# stm32f407.net
KiCad netlist of a schematic drawn in EAGLE
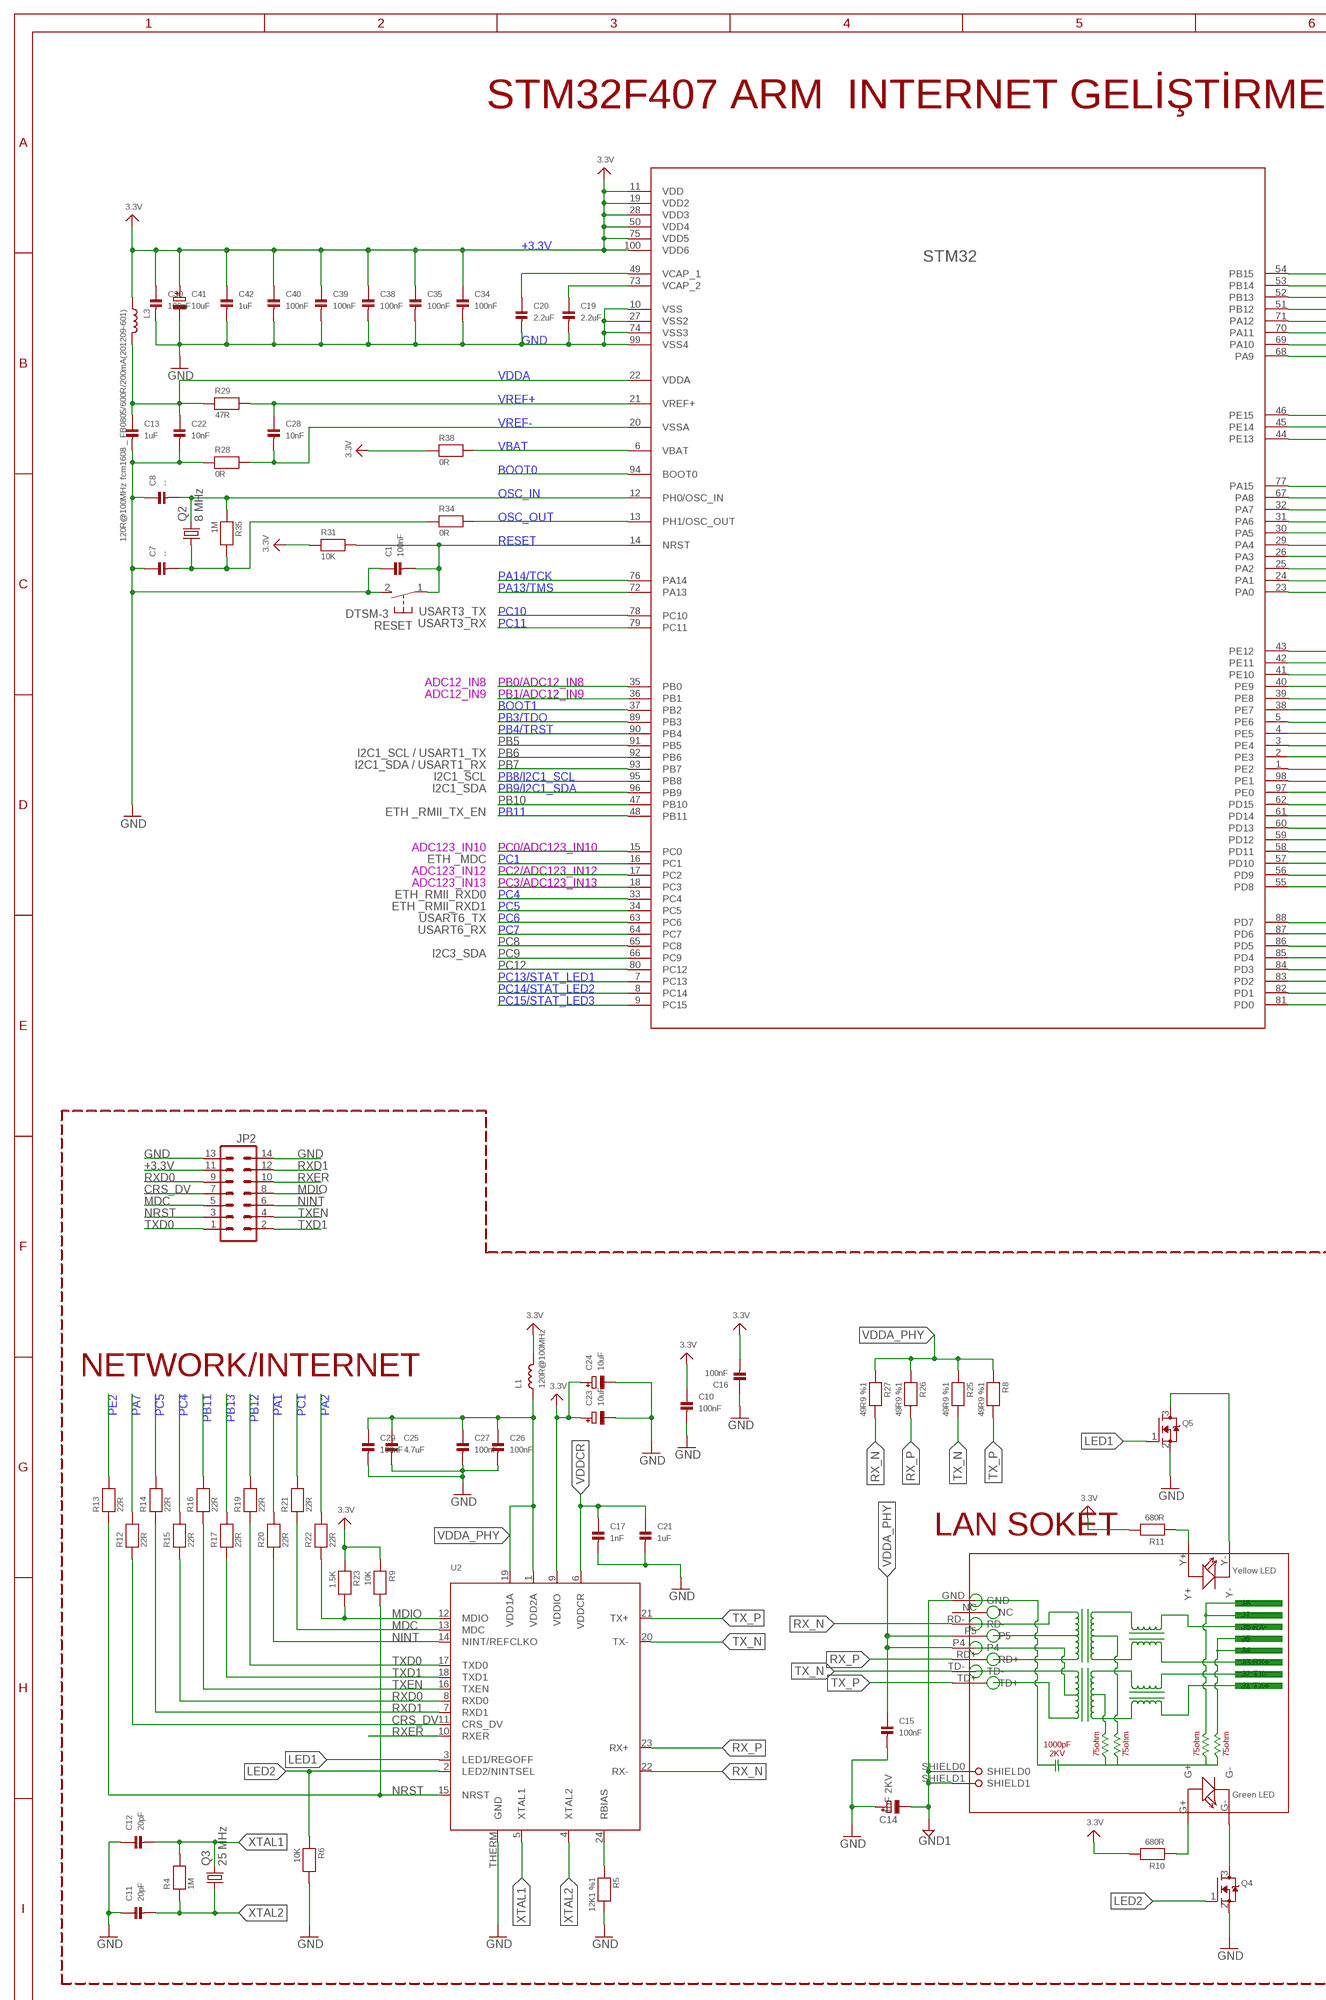
[diagram p0: schematic, sheet 1, part 1 of 2]
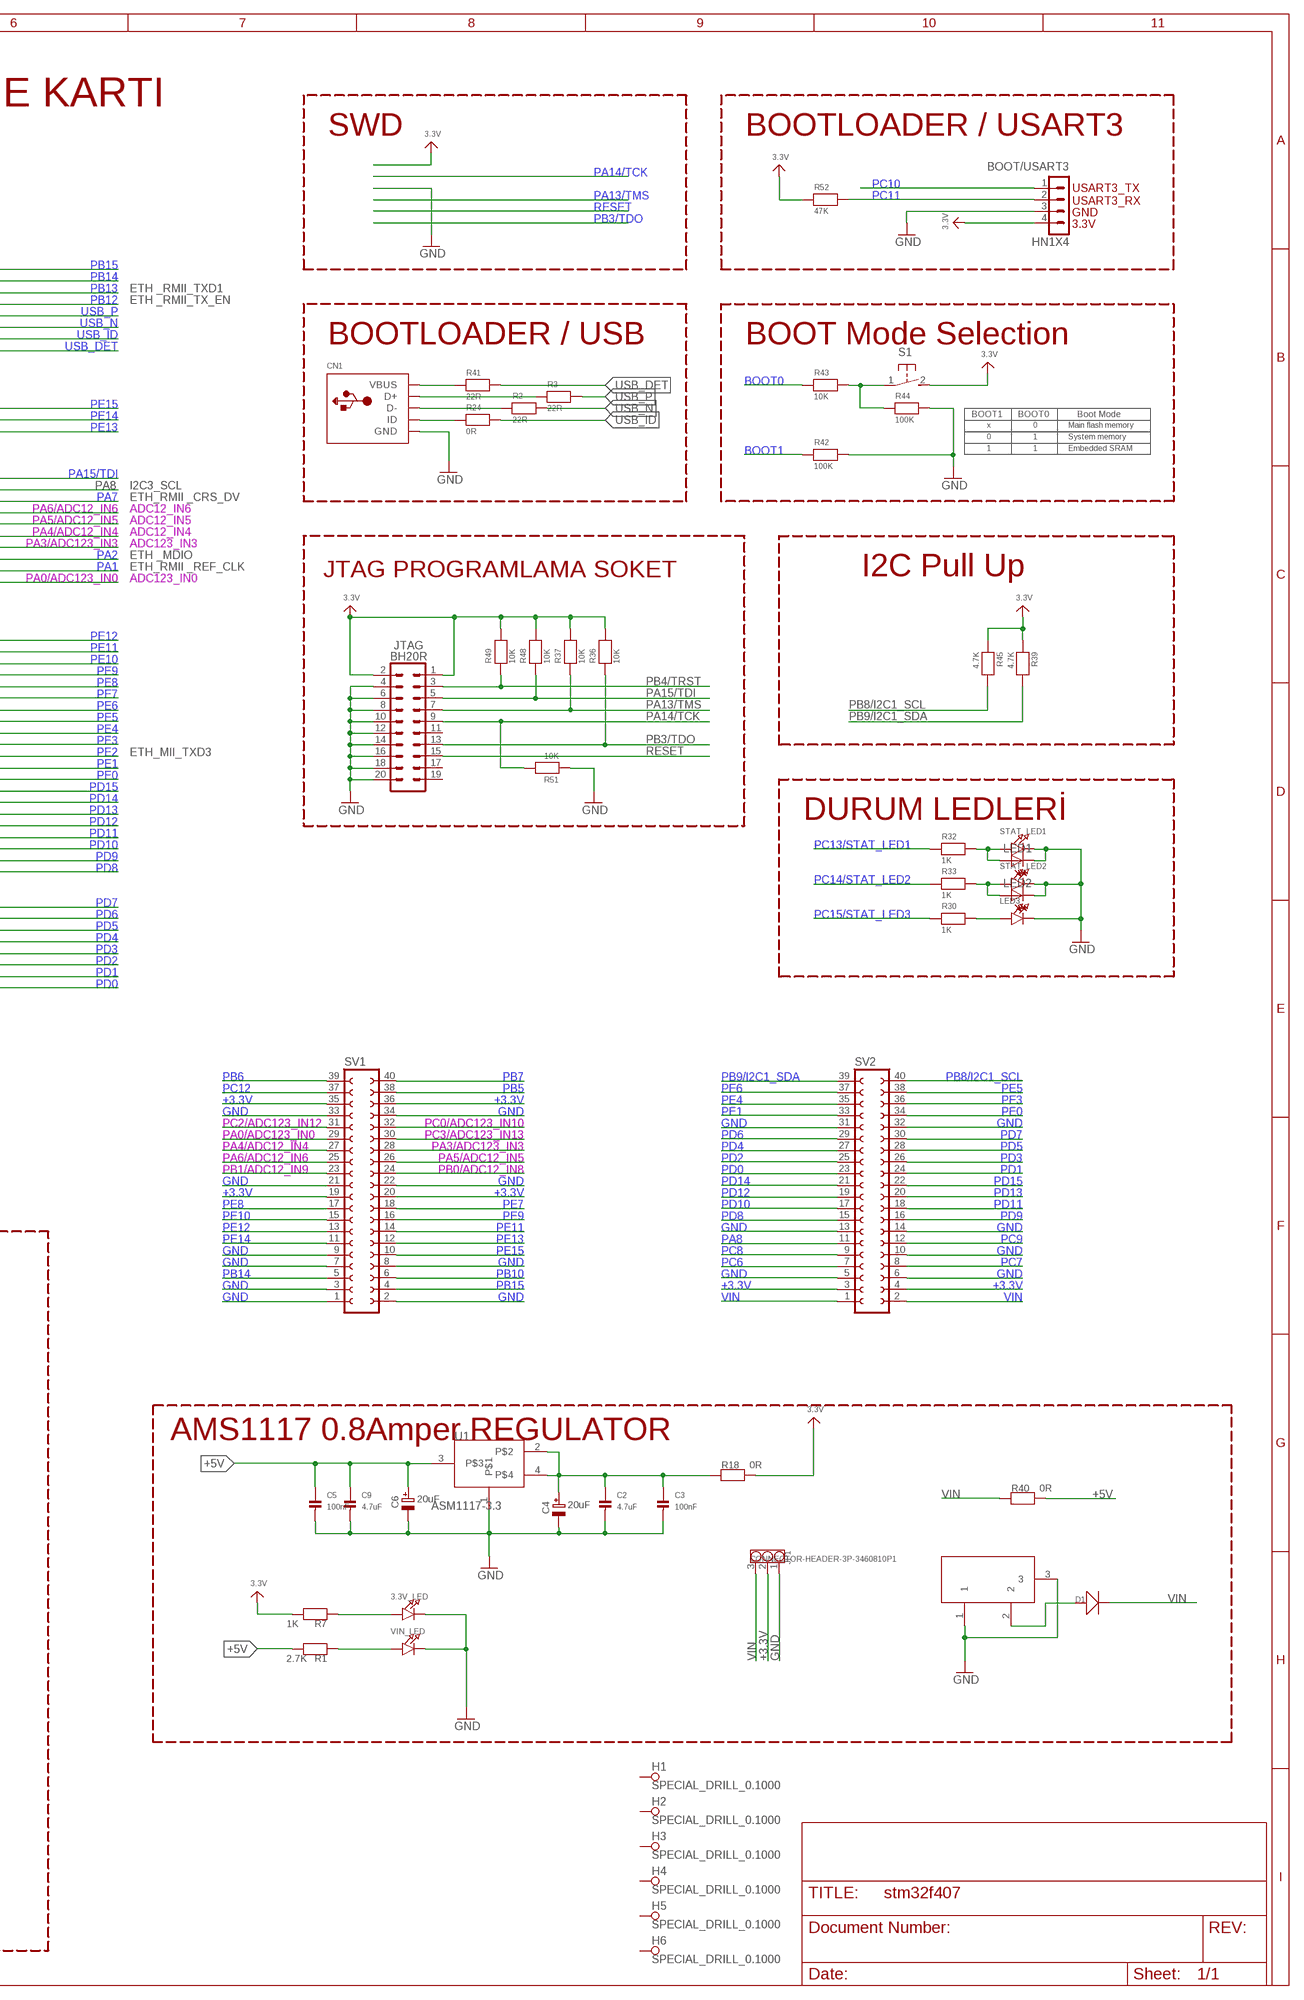
[diagram p1: schematic, sheet 1, part 2 of 2]

(export (version "E")
  (design (tool "Eeschema 10.0.6"))
  (components
    (comp (ref "3.3V_LED")
      (value "LED0805")
      (footprint "eagle-import:CHIPLED_0805")
      (libsource (lib "eagle-import") (part "LED0805"))
    )
    (comp (ref "BOOT/USART3")
      (value "HN1X4")
      (footprint "eagle-import:HN1X4")
      (libsource (lib "eagle-import") (part "CON4HN1X4"))
    )
    (comp (ref "C1")
      (value "100nF")
      (footprint "eagle-import:_0603")
      (libsource (lib "eagle-import") (part "CAP_CERAMIC_0603"))
    )
    (comp (ref "C2")
      (value "4.7uF")
      (footprint "eagle-import:0805")
      (libsource (lib "eagle-import") (part "CAP_CERAMIC0805"))
    )
    (comp (ref "C3")
      (value "100nF")
      (footprint "eagle-import:0805")
      (libsource (lib "eagle-import") (part "CAP_CERAMIC0805"))
    )
    (comp (ref "C4")
      (value "20uF")
      (footprint "eagle-import:EIA3528-21_B-R")
      (libsource (lib "eagle-import") (part "CAP_TANTALUMB/3528_REFLOW"))
    )
    (comp (ref "C5")
      (value "100nF")
      (footprint "eagle-import:0805")
      (libsource (lib "eagle-import") (part "CAP_CERAMIC0805"))
    )
    (comp (ref "C6")
      (value "20uF")
      (footprint "eagle-import:EIA3528-21_B-R")
      (libsource (lib "eagle-import") (part "CAP_TANTALUMB/3528_REFLOW"))
    )
    (comp (ref "C7")
      (value "--")
      (footprint "eagle-import:_0603")
      (libsource (lib "eagle-import") (part "CAP_CERAMIC_0603"))
    )
    (comp (ref "C8")
      (value "--")
      (footprint "eagle-import:_0603")
      (libsource (lib "eagle-import") (part "CAP_CERAMIC_0603"))
    )
    (comp (ref "C9")
      (value "4.7uF")
      (footprint "eagle-import:0805")
      (libsource (lib "eagle-import") (part "CAP_CERAMIC0805"))
    )
    (comp (ref "C10")
      (value "100nF")
      (footprint "eagle-import:_0603")
      (libsource (lib "eagle-import") (part "CAP_CERAMIC_0603"))
    )
    (comp (ref "C11")
      (value "20pF")
      (footprint "eagle-import:_0603")
      (libsource (lib "eagle-import") (part "CAP_CERAMIC_0603"))
    )
    (comp (ref "C12")
      (value "20pF")
      (footprint "eagle-import:_0603")
      (libsource (lib "eagle-import") (part "CAP_CERAMIC_0603"))
    )
    (comp (ref "C13")
      (value "1uF")
      (footprint "eagle-import:_0805")
      (libsource (lib "eagle-import") (part "CAP_CERAMIC_0805"))
    )
    (comp (ref "C14")
      (value "1nF 2KV")
      (footprint "eagle-import:EIA3528-21_B-R")
      (libsource (lib "eagle-import") (part "CAP_TANTALUMB/3528_REFLOW"))
    )
    (comp (ref "C15")
      (value "100nF")
      (footprint "eagle-import:_0805")
      (libsource (lib "eagle-import") (part "CAP_CERAMIC_0805"))
    )
    (comp (ref "C16")
      (value "100nF")
      (footprint "eagle-import:_0603")
      (libsource (lib "eagle-import") (part "CAP_CERAMIC_0603"))
    )
    (comp (ref "C17")
      (value "1nF")
      (footprint "eagle-import:_0603")
      (libsource (lib "eagle-import") (part "CAP_CERAMIC_0603"))
    )
    (comp (ref "C19")
      (value "2.2uF")
      (footprint "eagle-import:1206")
      (libsource (lib "eagle-import") (part "CAP_CERAMIC1206"))
    )
    (comp (ref "C20")
      (value "2.2uF")
      (footprint "eagle-import:1206")
      (libsource (lib "eagle-import") (part "CAP_CERAMIC1206"))
    )
    (comp (ref "C21")
      (value "1uF")
      (footprint "eagle-import:_0805")
      (libsource (lib "eagle-import") (part "CAP_CERAMIC_0805"))
    )
    (comp (ref "C22")
      (value "10nF")
      (footprint "eagle-import:_0603")
      (libsource (lib "eagle-import") (part "CAP_CERAMIC_0603"))
    )
    (comp (ref "C23")
      (value "10uF")
      (footprint "eagle-import:EIA3528-21_B-R")
      (libsource (lib "eagle-import") (part "CAP_TANTALUMB/3528_REFLOW"))
    )
    (comp (ref "C24")
      (value "10uF")
      (footprint "eagle-import:EIA3528-21_B-R")
      (libsource (lib "eagle-import") (part "CAP_TANTALUMB/3528_REFLOW"))
    )
    (comp (ref "C25")
      (value "4.7uF")
      (footprint "eagle-import:_0805")
      (libsource (lib "eagle-import") (part "CAP_CERAMIC_0805"))
    )
    (comp (ref "C26")
      (value "100nF")
      (footprint "eagle-import:_0603")
      (libsource (lib "eagle-import") (part "CAP_CERAMIC_0603"))
    )
    (comp (ref "C27")
      (value "100nF")
      (footprint "eagle-import:_0603")
      (libsource (lib "eagle-import") (part "CAP_CERAMIC_0603"))
    )
    (comp (ref "C28")
      (value "10nF")
      (footprint "eagle-import:_0603")
      (libsource (lib "eagle-import") (part "CAP_CERAMIC_0603"))
    )
    (comp (ref "C29")
      (value "100nF")
      (footprint "eagle-import:_0603")
      (libsource (lib "eagle-import") (part "CAP_CERAMIC_0603"))
    )
    (comp (ref "C30")
      (value "100nF")
      (footprint "eagle-import:_0603")
      (libsource (lib "eagle-import") (part "CAP_CERAMIC_0603"))
    )
    (comp (ref "C34")
      (value "100nF")
      (footprint "eagle-import:_0603")
      (libsource (lib "eagle-import") (part "CAP_CERAMIC_0603"))
    )
    (comp (ref "C35")
      (value "100nF")
      (footprint "eagle-import:_0603")
      (libsource (lib "eagle-import") (part "CAP_CERAMIC_0603"))
    )
    (comp (ref "C38")
      (value "100nF")
      (footprint "eagle-import:_0603")
      (libsource (lib "eagle-import") (part "CAP_CERAMIC_0603"))
    )
    (comp (ref "C39")
      (value "100nF")
      (footprint "eagle-import:_0603")
      (libsource (lib "eagle-import") (part "CAP_CERAMIC_0603"))
    )
    (comp (ref "C40")
      (value "100nF")
      (footprint "eagle-import:_0603")
      (libsource (lib "eagle-import") (part "CAP_CERAMIC_0603"))
    )
    (comp (ref "C41")
      (value "10uF")
      (footprint "eagle-import:EIA3528-21_B-R")
      (libsource (lib "eagle-import") (part "CAP_TANTALUMB/3528_REFLOW"))
    )
    (comp (ref "C42")
      (value "1uF")
      (footprint "eagle-import:_0805")
      (libsource (lib "eagle-import") (part "CAP_CERAMIC_0805"))
    )
    (comp (ref "CN1")
      (value "USBMINIBLARGE")
      (footprint "eagle-import:USB-MINIB_LARGER")
      (libsource (lib "eagle-import") (part "USBMINIBLARGE"))
    )
    (comp (ref "D1")
      (value "D-D1206")
      (footprint "eagle-import:LL-34")
      (libsource (lib "eagle-import") (part "D-D1206"))
    )
    (comp (ref "H1")
      (value "SPECIAL_DRILL_0.1000")
      (footprint "eagle-import:PAD_0.1000")
      (libsource (lib "eagle-import") (part "SPECIAL_DRILL_0.1000"))
    )
    (comp (ref "H2")
      (value "SPECIAL_DRILL_0.1000")
      (footprint "eagle-import:PAD_0.1000")
      (libsource (lib "eagle-import") (part "SPECIAL_DRILL_0.1000"))
    )
    (comp (ref "H3")
      (value "SPECIAL_DRILL_0.1000")
      (footprint "eagle-import:PAD_0.1000")
      (libsource (lib "eagle-import") (part "SPECIAL_DRILL_0.1000"))
    )
    (comp (ref "H4")
      (value "SPECIAL_DRILL_0.1000")
      (footprint "eagle-import:PAD_0.1000")
      (libsource (lib "eagle-import") (part "SPECIAL_DRILL_0.1000"))
    )
    (comp (ref "H5")
      (value "SPECIAL_DRILL_0.1000")
      (footprint "eagle-import:PAD_0.1000")
      (libsource (lib "eagle-import") (part "SPECIAL_DRILL_0.1000"))
    )
    (comp (ref "H6")
      (value "SPECIAL_DRILL_0.1000")
      (footprint "eagle-import:PAD_0.1000")
      (libsource (lib "eagle-import") (part "SPECIAL_DRILL_0.1000"))
    )
    (comp (ref "JP1")
      (value "CONNECTOR-HEADER-3P-3460810P1")
      (footprint "eagle-import:1X3P-2.54-2.54-11.6-3.0-BLACK-MALE")
      (libsource (lib "eagle-import") (part "CONNECTOR-HEADER-3P-3460810P1"))
    )
    (comp (ref "JP2")
      (value "MA07-2")
      (footprint "eagle-import:MA07-2")
      (libsource (lib "eagle-import") (part "MA07-2"))
    )
    (comp (ref "JTAG")
      (value "BH20R")
      (footprint "eagle-import:BH20R")
      (libsource (lib "eagle-import") (part "ML20R"))
    )
    (comp (ref "L1")
      (value "120R@100MHz")
      (footprint "eagle-import:_0805")
      (libsource (lib "eagle-import") (part "INDUCTOR_0805"))
    )
    (comp (ref "L3")
      (value "120R@100MHz fcm1608 _ FB0805/600R/200mA(201209-601)")
      (footprint "eagle-import:_0805")
      (libsource (lib "eagle-import") (part "INDUCTOR_0805"))
    )
    (comp (ref "LED1")
      (value "LED5MM")
      (footprint "eagle-import:LED5MM")
      (libsource (lib "eagle-import") (part "LED5MM"))
    )
    (comp (ref "LED2")
      (value "LED5MM")
      (footprint "eagle-import:LED5MM")
      (libsource (lib "eagle-import") (part "LED5MM"))
    )
    (comp (ref "LED3")
      (value "LED0805")
      (footprint "eagle-import:CHIPLED_0805")
      (libsource (lib "eagle-import") (part "LED0805"))
    )
    (comp (ref "Q2")
      (value "8 MHz")
      (footprint "eagle-import:HC49UP")
      (libsource (lib "eagle-import") (part "CRYSTALHC49UP"))
    )
    (comp (ref "Q3")
      (value "25 MHz")
      (footprint "eagle-import:HC49UP")
      (libsource (lib "eagle-import") (part "CRYSTALHC49UP"))
    )
    (comp (ref "Q4")
      (value "MOSFET-NWIDE")
      (footprint "eagle-import:SOT23-WIDE")
      (libsource (lib "eagle-import") (part "MOSFET-NWIDE"))
    )
    (comp (ref "Q5")
      (value "MOSFET-NWIDE")
      (footprint "eagle-import:SOT23-WIDE")
      (libsource (lib "eagle-import") (part "MOSFET-NWIDE"))
    )
    (comp (ref "R1")
      (value "2.7K")
      (footprint "eagle-import:_0603")
      (libsource (lib "eagle-import") (part "RESISTOR_0603"))
    )
    (comp (ref "R2")
      (value "22R")
      (footprint "eagle-import:_0603")
      (libsource (lib "eagle-import") (part "RESISTOR_0603"))
    )
    (comp (ref "R3")
      (value "22R")
      (footprint "eagle-import:_0603")
      (libsource (lib "eagle-import") (part "RESISTOR_0603"))
    )
    (comp (ref "R4")
      (value "1M")
      (footprint "eagle-import:_0603")
      (libsource (lib "eagle-import") (part "RESISTOR_0603"))
    )
    (comp (ref "R5")
      (value "12K1 %1")
      (footprint "eagle-import:_0603")
      (libsource (lib "eagle-import") (part "RESISTOR_0603"))
    )
    (comp (ref "R6")
      (value "10K")
      (footprint "eagle-import:_0603")
      (libsource (lib "eagle-import") (part "RESISTOR_0603"))
    )
    (comp (ref "R7")
      (value "1K")
      (footprint "eagle-import:_0603")
      (libsource (lib "eagle-import") (part "RESISTOR_0603"))
    )
    (comp (ref "R8")
      (value "49R9 %1")
      (footprint "eagle-import:_0603")
      (libsource (lib "eagle-import") (part "RESISTOR_0603"))
    )
    (comp (ref "R9")
      (value "10K")
      (footprint "eagle-import:_0603")
      (libsource (lib "eagle-import") (part "RESISTOR_0603"))
    )
    (comp (ref "R10")
      (value "680R")
      (footprint "eagle-import:_0805")
      (libsource (lib "eagle-import") (part "RESISTOR_0805"))
    )
    (comp (ref "R11")
      (value "680R")
      (footprint "eagle-import:_0805")
      (libsource (lib "eagle-import") (part "RESISTOR_0805"))
    )
    (comp (ref "R12")
      (value "22R")
      (footprint "eagle-import:_0603")
      (libsource (lib "eagle-import") (part "RESISTOR_0603"))
    )
    (comp (ref "R13")
      (value "22R")
      (footprint "eagle-import:_0603")
      (libsource (lib "eagle-import") (part "RESISTOR_0603"))
    )
    (comp (ref "R14")
      (value "22R")
      (footprint "eagle-import:_0603")
      (libsource (lib "eagle-import") (part "RESISTOR_0603"))
    )
    (comp (ref "R15")
      (value "22R")
      (footprint "eagle-import:_0603")
      (libsource (lib "eagle-import") (part "RESISTOR_0603"))
    )
    (comp (ref "R16")
      (value "22R")
      (footprint "eagle-import:_0603")
      (libsource (lib "eagle-import") (part "RESISTOR_0603"))
    )
    (comp (ref "R17")
      (value "22R")
      (footprint "eagle-import:_0603")
      (libsource (lib "eagle-import") (part "RESISTOR_0603"))
    )
    (comp (ref "R18")
      (value "0R")
      (footprint "eagle-import:0805")
      (libsource (lib "eagle-import") (part "RESISTOR0805"))
    )
    (comp (ref "R19")
      (value "22R")
      (footprint "eagle-import:_0603")
      (libsource (lib "eagle-import") (part "RESISTOR_0603"))
    )
    (comp (ref "R20")
      (value "22R")
      (footprint "eagle-import:_0603")
      (libsource (lib "eagle-import") (part "RESISTOR_0603"))
    )
    (comp (ref "R21")
      (value "22R")
      (footprint "eagle-import:_0603")
      (libsource (lib "eagle-import") (part "RESISTOR_0603"))
    )
    (comp (ref "R22")
      (value "22R")
      (footprint "eagle-import:_0603")
      (libsource (lib "eagle-import") (part "RESISTOR_0603"))
    )
    (comp (ref "R23")
      (value "1.5K")
      (footprint "eagle-import:_0603")
      (libsource (lib "eagle-import") (part "RESISTOR_0603"))
    )
    (comp (ref "R24")
      (value "0R")
      (footprint "eagle-import:_0603")
      (libsource (lib "eagle-import") (part "RESISTOR_0603"))
    )
    (comp (ref "R25")
      (value "49R9 %1")
      (footprint "eagle-import:_0603")
      (libsource (lib "eagle-import") (part "RESISTOR_0603"))
    )
    (comp (ref "R26")
      (value "49R9 %1")
      (footprint "eagle-import:_0603")
      (libsource (lib "eagle-import") (part "RESISTOR_0603"))
    )
    (comp (ref "R27")
      (value "49R9 %1")
      (footprint "eagle-import:_0603")
      (libsource (lib "eagle-import") (part "RESISTOR_0603"))
    )
    (comp (ref "R28")
      (value "0R")
      (footprint "eagle-import:_0603")
      (libsource (lib "eagle-import") (part "RESISTOR_0603"))
    )
    (comp (ref "R29")
      (value "47R")
      (footprint "eagle-import:_0603")
      (libsource (lib "eagle-import") (part "RESISTOR_0603"))
    )
    (comp (ref "R30")
      (value "1K")
      (footprint "eagle-import:_0603")
      (libsource (lib "eagle-import") (part "RESISTOR_0603"))
    )
    (comp (ref "R31")
      (value "10K")
      (footprint "eagle-import:_0603")
      (libsource (lib "eagle-import") (part "RESISTOR_0603"))
    )
    (comp (ref "R32")
      (value "1K")
      (footprint "eagle-import:_0603")
      (libsource (lib "eagle-import") (part "RESISTOR_0603"))
    )
    (comp (ref "R33")
      (value "1K")
      (footprint "eagle-import:_0603")
      (libsource (lib "eagle-import") (part "RESISTOR_0603"))
    )
    (comp (ref "R34")
      (value "0R")
      (footprint "eagle-import:_0603")
      (libsource (lib "eagle-import") (part "RESISTOR_0603"))
    )
    (comp (ref "R35")
      (value "1M")
      (footprint "eagle-import:_0603")
      (libsource (lib "eagle-import") (part "RESISTOR_0603"))
    )
    (comp (ref "R36")
      (value "10K")
      (footprint "eagle-import:_0603")
      (libsource (lib "eagle-import") (part "RESISTOR_0603"))
    )
    (comp (ref "R37")
      (value "10K")
      (footprint "eagle-import:_0603")
      (libsource (lib "eagle-import") (part "RESISTOR_0603"))
    )
    (comp (ref "R38")
      (value "0R")
      (footprint "eagle-import:_0603")
      (libsource (lib "eagle-import") (part "RESISTOR_0603"))
    )
    (comp (ref "R39")
      (value "4.7K")
      (footprint "eagle-import:1206")
      (libsource (lib "eagle-import") (part "RESISTOR1206"))
    )
    (comp (ref "R40")
      (value "0R")
      (footprint "eagle-import:0805")
      (libsource (lib "eagle-import") (part "RESISTOR0805"))
    )
    (comp (ref "R41")
      (value "22R")
      (footprint "eagle-import:_0603")
      (libsource (lib "eagle-import") (part "RESISTOR_0603"))
    )
    (comp (ref "R42")
      (value "100K")
      (footprint "eagle-import:_0603")
      (libsource (lib "eagle-import") (part "RESISTOR_0603"))
    )
    (comp (ref "R43")
      (value "10K")
      (footprint "eagle-import:_0603")
      (libsource (lib "eagle-import") (part "RESISTOR_0603"))
    )
    (comp (ref "R44")
      (value "100K")
      (footprint "eagle-import:_0603")
      (libsource (lib "eagle-import") (part "RESISTOR_0603"))
    )
    (comp (ref "R45")
      (value "4.7K")
      (footprint "eagle-import:1206")
      (libsource (lib "eagle-import") (part "RESISTOR1206"))
    )
    (comp (ref "R48")
      (value "10K")
      (footprint "eagle-import:_0603")
      (libsource (lib "eagle-import") (part "RESISTOR_0603"))
    )
    (comp (ref "R49")
      (value "10K")
      (footprint "eagle-import:_0603")
      (libsource (lib "eagle-import") (part "RESISTOR_0603"))
    )
    (comp (ref "R51")
      (value "10K")
      (footprint "eagle-import:_0603")
      (libsource (lib "eagle-import") (part "RESISTOR_0603"))
    )
    (comp (ref "R52")
      (value "47K")
      (footprint "eagle-import:_0603")
      (libsource (lib "eagle-import") (part "RESISTOR_0603"))
    )
    (comp (ref "RESET")
      (value "DTSM-3")
      (footprint "eagle-import:DTSM-3")
      (libsource (lib "eagle-import") (part "DTSM-3"))
    )
    (comp (ref "RJ1")
      (value "HR911105A")
      (footprint "eagle-import:HR911105A")
      (libsource (lib "eagle-import") (part "HR911105A"))
    )
    (comp (ref "S1")
      (value "31-XX")
      (footprint "eagle-import:B3F-31XX")
      (fields (field (name "MPN") "B3F-3100"))
      (libsource (lib "eagle-import") (part "31-XX"))
    )
    (comp (ref "STAT_LED1")
      (value "LED0805")
      (footprint "eagle-import:CHIPLED_0805")
      (libsource (lib "eagle-import") (part "LED0805"))
    )
    (comp (ref "STAT_LED2")
      (value "LED0805")
      (footprint "eagle-import:CHIPLED_0805")
      (libsource (lib "eagle-import") (part "LED0805"))
    )
    (comp (ref "STM32")
      (value "STM32F407")
      (footprint "eagle-import:100LQFP")
      (libsource (lib "eagle-import") (part "STM32F407"))
    )
    (comp (ref "SV1")
      (value "FE20-2")
      (footprint "eagle-import:FE20-2")
      (libsource (lib "eagle-import") (part "FE20-2"))
    )
    (comp (ref "SV2")
      (value "FE20-2")
      (footprint "eagle-import:FE20-2")
      (libsource (lib "eagle-import") (part "FE20-2"))
    )
    (comp (ref "U1")
      (value "ASM1117-3.3")
      (footprint "eagle-import:SOT223")
      (libsource (lib "eagle-import") (part "ASM1117-3.3"))
    )
    (comp (ref "U2")
      (value "LAN8720")
      (footprint "eagle-import:QFN24_4MM")
      (libsource (lib "eagle-import") (part "LAN8720"))
    )
    (comp (ref "VIN_LED")
      (value "LED0805")
      (footprint "eagle-import:CHIPLED_0805")
      (libsource (lib "eagle-import") (part "LED0805"))
    )
    (comp (ref "X1")
      (value "DC21MMX")
      (footprint "eagle-import:DC-21MM")
      (libsource (lib "eagle-import") (part "DC21MMX"))
    )
  )
  (nets
    (net (code "1") (name "+5V") (class "Default")
      (node (ref "C5") (pin "1") (pinfunction "P$1_1") (pintype "passive"))
      (node (ref "C6") (pin "+") (pinfunction "+_+") (pintype "passive"))
      (node (ref "C9") (pin "1") (pinfunction "P$1_1") (pintype "passive"))
      (node (ref "R1") (pin "2") (pinfunction "2_2") (pintype "passive"))
      (node (ref "R40") (pin "2") (pinfunction "2_2") (pintype "passive"))
      (node (ref "U1") (pin "3") (pinfunction "P$3_3") (pintype "bidirectional"))
    )
    (net (code "2") (name "/BOOT0") (class "Default")
      (node (ref "R43") (pin "1") (pinfunction "1_1") (pintype "passive"))
      (node (ref "STM32") (pin "94") (pinfunction "BOOT0_94") (pintype "bidirectional"))
    )
    (net (code "3") (name "/BOOT1") (class "Default")
      (node (ref "R42") (pin "1") (pinfunction "1_1") (pintype "passive"))
      (node (ref "STM32") (pin "37") (pinfunction "PB2_37") (pintype "bidirectional"))
    )
    (net (code "4") (name "/CRS_DV") (class "Default")
      (node (ref "JP2") (pin "7") (pinfunction "7_7") (pintype "passive"))
      (node (ref "R12") (pin "1") (pinfunction "1_1") (pintype "passive"))
      (node (ref "U2") (pin "11") (pinfunction "CRS_DV_11") (pintype "bidirectional"))
    )
    (net (code "5") (name "/MDC") (class "Default")
      (node (ref "JP2") (pin "5") (pinfunction "5_5") (pintype "passive"))
      (node (ref "R21") (pin "1") (pinfunction "1_1") (pintype "passive"))
      (node (ref "U2") (pin "13") (pinfunction "MDC_13") (pintype "bidirectional"))
    )
    (net (code "6") (name "/MDIO") (class "Default")
      (node (ref "JP2") (pin "8") (pinfunction "8_8") (pintype "passive"))
      (node (ref "R22") (pin "1") (pinfunction "1_1") (pintype "passive"))
      (node (ref "R23") (pin "2") (pinfunction "2_2") (pintype "passive"))
      (node (ref "U2") (pin "12") (pinfunction "MDIO_12") (pintype "bidirectional"))
    )
    (net (code "7") (name "/NINT") (class "Default")
      (node (ref "JP2") (pin "6") (pinfunction "6_6") (pintype "passive"))
      (node (ref "R20") (pin "1") (pinfunction "1_1") (pintype "passive"))
      (node (ref "U2") (pin "14") (pinfunction "NINT/REFCLKO_14") (pintype "bidirectional"))
    )
    (net (code "8") (name "/NRST") (class "Default")
      (node (ref "JP2") (pin "3") (pinfunction "3_3") (pintype "passive"))
      (node (ref "R13") (pin "1") (pinfunction "1_1") (pintype "passive"))
      (node (ref "R9") (pin "2") (pinfunction "2_2") (pintype "passive"))
      (node (ref "U2") (pin "15") (pinfunction "NRST_15") (pintype "bidirectional"))
    )
    (net (code "9") (name "/OSC_IN") (class "Default")
      (node (ref "C8") (pin "2") (pinfunction "P$2_2") (pintype "passive"))
      (node (ref "Q2") (pin "2") (pinfunction "2_2") (pintype "passive"))
      (node (ref "R35") (pin "1") (pinfunction "1_1") (pintype "passive"))
      (node (ref "STM32") (pin "12") (pinfunction "PH0/OSC_IN_12") (pintype "bidirectional"))
    )
    (net (code "10") (name "/OSC_OUT") (class "Default")
      (node (ref "R34") (pin "2") (pinfunction "2_2") (pintype "passive"))
      (node (ref "STM32") (pin "13") (pinfunction "PH1/OSC_OUT_13") (pintype "bidirectional"))
    )
    (net (code "11") (name "/PA0{slash}ADC123_IN0") (class "Default")
      (node (ref "STM32") (pin "23") (pinfunction "PA0_23") (pintype "bidirectional"))
      (node (ref "SV1") (pin "29") (pinfunction "29_29") (pintype "passive"))
    )
    (net (code "12") (name "/PA1") (class "Default")
      (node (ref "R20") (pin "2") (pinfunction "2_2") (pintype "passive"))
      (node (ref "STM32") (pin "24") (pinfunction "PA1_24") (pintype "bidirectional"))
    )
    (net (code "13") (name "/PA2") (class "Default")
      (node (ref "R22") (pin "2") (pinfunction "2_2") (pintype "passive"))
      (node (ref "STM32") (pin "25") (pinfunction "PA2_25") (pintype "bidirectional"))
    )
    (net (code "14") (name "/PA3{slash}ADC123_IN3") (class "Default")
      (node (ref "STM32") (pin "26") (pinfunction "PA3_26") (pintype "bidirectional"))
      (node (ref "SV1") (pin "28") (pinfunction "28_28") (pintype "passive"))
    )
    (net (code "15") (name "/PA4{slash}ADC12_IN4") (class "Default")
      (node (ref "STM32") (pin "29") (pinfunction "PA4_29") (pintype "bidirectional"))
      (node (ref "SV1") (pin "27") (pinfunction "27_27") (pintype "passive"))
    )
    (net (code "16") (name "/PA5{slash}ADC12_IN5") (class "Default")
      (node (ref "STM32") (pin "30") (pinfunction "PA5_30") (pintype "bidirectional"))
      (node (ref "SV1") (pin "26") (pinfunction "26_26") (pintype "passive"))
    )
    (net (code "17") (name "/PA6{slash}ADC12_IN6") (class "Default")
      (node (ref "STM32") (pin "31") (pinfunction "PA6_31") (pintype "bidirectional"))
      (node (ref "SV1") (pin "25") (pinfunction "25_25") (pintype "passive"))
    )
    (net (code "18") (name "/PA7") (class "Default")
      (node (ref "R12") (pin "2") (pinfunction "2_2") (pintype "passive"))
      (node (ref "STM32") (pin "32") (pinfunction "PA7_32") (pintype "bidirectional"))
    )
    (net (code "19") (name "/PA8") (class "Default")
      (node (ref "STM32") (pin "67") (pinfunction "PA8_67") (pintype "bidirectional"))
      (node (ref "SV2") (pin "11") (pinfunction "11_11") (pintype "passive"))
    )
    (net (code "20") (name "/PA13{slash}TMS") (class "Default")
      (node (ref "JTAG") (pin "7") (pinfunction "7_7") (pintype "passive"))
      (node (ref "R37") (pin "1") (pinfunction "1_1") (pintype "passive"))
      (node (ref "STM32") (pin "72") (pinfunction "PA13_72") (pintype "bidirectional"))
    )
    (net (code "21") (name "/PA14{slash}TCK") (class "Default")
      (node (ref "JTAG") (pin "9") (pinfunction "9_9") (pintype "passive"))
      (node (ref "R51") (pin "2") (pinfunction "2_2") (pintype "passive"))
      (node (ref "STM32") (pin "76") (pinfunction "PA14_76") (pintype "bidirectional"))
    )
    (net (code "22") (name "/PA15{slash}TDI") (class "Default")
      (node (ref "JTAG") (pin "5") (pinfunction "5_5") (pintype "passive"))
      (node (ref "R48") (pin "1") (pinfunction "1_1") (pintype "passive"))
      (node (ref "STM32") (pin "77") (pinfunction "PA15_77") (pintype "bidirectional"))
    )
    (net (code "23") (name "/PB0{slash}ADC12_IN8") (class "Default")
      (node (ref "STM32") (pin "35") (pinfunction "PB0_35") (pintype "bidirectional"))
      (node (ref "SV1") (pin "24") (pinfunction "24_24") (pintype "passive"))
    )
    (net (code "24") (name "/PB1{slash}ADC12_IN9") (class "Default")
      (node (ref "STM32") (pin "36") (pinfunction "PB1_36") (pintype "bidirectional"))
      (node (ref "SV1") (pin "23") (pinfunction "23_23") (pintype "passive"))
    )
    (net (code "25") (name "/PB3{slash}TDO") (class "Default")
      (node (ref "JTAG") (pin "13") (pinfunction "13_13") (pintype "passive"))
      (node (ref "R36") (pin "1") (pinfunction "1_1") (pintype "passive"))
      (node (ref "STM32") (pin "89") (pinfunction "PB3_89") (pintype "bidirectional"))
    )
    (net (code "26") (name "/PB4{slash}TRST") (class "Default")
      (node (ref "JTAG") (pin "3") (pinfunction "3_3") (pintype "passive"))
      (node (ref "R49") (pin "1") (pinfunction "1_1") (pintype "passive"))
      (node (ref "STM32") (pin "90") (pinfunction "PB4_90") (pintype "bidirectional"))
    )
    (net (code "27") (name "/PB5") (class "Default")
      (node (ref "STM32") (pin "91") (pinfunction "PB5_91") (pintype "bidirectional"))
      (node (ref "SV1") (pin "38") (pinfunction "38_38") (pintype "passive"))
    )
    (net (code "28") (name "/PB6") (class "Default")
      (node (ref "STM32") (pin "92") (pinfunction "PB6_92") (pintype "bidirectional"))
      (node (ref "SV1") (pin "39") (pinfunction "39_39") (pintype "passive"))
    )
    (net (code "29") (name "/PB7") (class "Default")
      (node (ref "STM32") (pin "93") (pinfunction "PB7_93") (pintype "bidirectional"))
      (node (ref "SV1") (pin "40") (pinfunction "40_40") (pintype "passive"))
    )
    (net (code "30") (name "/PB8{slash}I2C1_SCL") (class "Default")
      (node (ref "R45") (pin "2") (pinfunction "2_2") (pintype "passive"))
      (node (ref "STM32") (pin "95") (pinfunction "PB8_95") (pintype "bidirectional"))
      (node (ref "SV2") (pin "40") (pinfunction "40_40") (pintype "passive"))
    )
    (net (code "31") (name "/PB9{slash}I2C1_SDA") (class "Default")
      (node (ref "R39") (pin "2") (pinfunction "2_2") (pintype "passive"))
      (node (ref "STM32") (pin "96") (pinfunction "PB9_96") (pintype "bidirectional"))
      (node (ref "SV2") (pin "39") (pinfunction "39_39") (pintype "passive"))
    )
    (net (code "32") (name "/PB10") (class "Default")
      (node (ref "STM32") (pin "47") (pinfunction "PB10_47") (pintype "bidirectional"))
      (node (ref "SV1") (pin "6") (pinfunction "6_6") (pintype "passive"))
    )
    (net (code "33") (name "/PB11") (class "Default")
      (node (ref "R16") (pin "2") (pinfunction "2_2") (pintype "passive"))
      (node (ref "STM32") (pin "48") (pinfunction "PB11_48") (pintype "bidirectional"))
    )
    (net (code "34") (name "/PB12") (class "Default")
      (node (ref "R19") (pin "2") (pinfunction "2_2") (pintype "passive"))
      (node (ref "STM32") (pin "51") (pinfunction "PB12_51") (pintype "bidirectional"))
    )
    (net (code "35") (name "/PB13") (class "Default")
      (node (ref "R17") (pin "2") (pinfunction "2_2") (pintype "passive"))
      (node (ref "STM32") (pin "52") (pinfunction "PB13_52") (pintype "bidirectional"))
    )
    (net (code "36") (name "/PB14") (class "Default")
      (node (ref "STM32") (pin "53") (pinfunction "PB14_53") (pintype "bidirectional"))
      (node (ref "SV1") (pin "5") (pinfunction "5_5") (pintype "passive"))
    )
    (net (code "37") (name "/PB15") (class "Default")
      (node (ref "STM32") (pin "54") (pinfunction "PB15_54") (pintype "bidirectional"))
      (node (ref "SV1") (pin "4") (pinfunction "4_4") (pintype "passive"))
    )
    (net (code "38") (name "/PC0{slash}ADC123_IN10") (class "Default")
      (node (ref "STM32") (pin "15") (pinfunction "PC0_15") (pintype "bidirectional"))
      (node (ref "SV1") (pin "32") (pinfunction "32_32") (pintype "passive"))
    )
    (net (code "39") (name "/PC1") (class "Default")
      (node (ref "R21") (pin "2") (pinfunction "2_2") (pintype "passive"))
      (node (ref "STM32") (pin "16") (pinfunction "PC1_16") (pintype "bidirectional"))
    )
    (net (code "40") (name "/PC2{slash}ADC123_IN12") (class "Default")
      (node (ref "STM32") (pin "17") (pinfunction "PC2_17") (pintype "bidirectional"))
      (node (ref "SV1") (pin "31") (pinfunction "31_31") (pintype "passive"))
    )
    (net (code "41") (name "/PC3{slash}ADC123_IN13") (class "Default")
      (node (ref "STM32") (pin "18") (pinfunction "PC3_18") (pintype "bidirectional"))
      (node (ref "SV1") (pin "30") (pinfunction "30_30") (pintype "passive"))
    )
    (net (code "42") (name "/PC4") (class "Default")
      (node (ref "R15") (pin "2") (pinfunction "2_2") (pintype "passive"))
      (node (ref "STM32") (pin "33") (pinfunction "PC4_33") (pintype "bidirectional"))
    )
    (net (code "43") (name "/PC5") (class "Default")
      (node (ref "R14") (pin "2") (pinfunction "2_2") (pintype "passive"))
      (node (ref "STM32") (pin "34") (pinfunction "PC5_34") (pintype "bidirectional"))
    )
    (net (code "44") (name "/PC6") (class "Default")
      (node (ref "STM32") (pin "63") (pinfunction "PC6_63") (pintype "bidirectional"))
      (node (ref "SV2") (pin "7") (pinfunction "7_7") (pintype "passive"))
    )
    (net (code "45") (name "/PC7") (class "Default")
      (node (ref "STM32") (pin "64") (pinfunction "PC7_64") (pintype "bidirectional"))
      (node (ref "SV2") (pin "8") (pinfunction "8_8") (pintype "passive"))
    )
    (net (code "46") (name "/PC8") (class "Default")
      (node (ref "STM32") (pin "65") (pinfunction "PC8_65") (pintype "bidirectional"))
      (node (ref "SV2") (pin "9") (pinfunction "9_9") (pintype "passive"))
    )
    (net (code "47") (name "/PC9") (class "Default")
      (node (ref "STM32") (pin "66") (pinfunction "PC9_66") (pintype "bidirectional"))
      (node (ref "SV2") (pin "12") (pinfunction "12_12") (pintype "passive"))
    )
    (net (code "48") (name "/PC10") (class "Default")
      (node (ref "BOOT/USART3") (pin "1") (pinfunction "1_1") (pintype "passive"))
      (node (ref "STM32") (pin "78") (pinfunction "PC10_78") (pintype "bidirectional"))
    )
    (net (code "49") (name "/PC11") (class "Default")
      (node (ref "BOOT/USART3") (pin "2") (pinfunction "2_2") (pintype "passive"))
      (node (ref "R52") (pin "2") (pinfunction "2_2") (pintype "passive"))
      (node (ref "STM32") (pin "79") (pinfunction "PC11_79") (pintype "bidirectional"))
    )
    (net (code "50") (name "/PC12") (class "Default")
      (node (ref "STM32") (pin "80") (pinfunction "PC12_80") (pintype "bidirectional"))
      (node (ref "SV1") (pin "37") (pinfunction "37_37") (pintype "passive"))
    )
    (net (code "51") (name "/PC13{slash}STAT_LED1") (class "Default")
      (node (ref "R32") (pin "1") (pinfunction "1_1") (pintype "passive"))
      (node (ref "STM32") (pin "7") (pinfunction "PC13_7") (pintype "bidirectional"))
    )
    (net (code "52") (name "/PC14{slash}STAT_LED2") (class "Default")
      (node (ref "R33") (pin "1") (pinfunction "1_1") (pintype "passive"))
      (node (ref "STM32") (pin "8") (pinfunction "PC14_8") (pintype "bidirectional"))
    )
    (net (code "53") (name "/PC15{slash}STAT_LED3") (class "Default")
      (node (ref "R30") (pin "1") (pinfunction "1_1") (pintype "passive"))
      (node (ref "STM32") (pin "9") (pinfunction "PC15_9") (pintype "bidirectional"))
    )
    (net (code "54") (name "/PD0") (class "Default")
      (node (ref "STM32") (pin "81") (pinfunction "PD0_81") (pintype "bidirectional"))
      (node (ref "SV2") (pin "23") (pinfunction "23_23") (pintype "passive"))
    )
    (net (code "55") (name "/PD1") (class "Default")
      (node (ref "STM32") (pin "82") (pinfunction "PD1_82") (pintype "bidirectional"))
      (node (ref "SV2") (pin "24") (pinfunction "24_24") (pintype "passive"))
    )
    (net (code "56") (name "/PD2") (class "Default")
      (node (ref "STM32") (pin "83") (pinfunction "PD2_83") (pintype "bidirectional"))
      (node (ref "SV2") (pin "25") (pinfunction "25_25") (pintype "passive"))
    )
    (net (code "57") (name "/PD3") (class "Default")
      (node (ref "STM32") (pin "84") (pinfunction "PD3_84") (pintype "bidirectional"))
      (node (ref "SV2") (pin "26") (pinfunction "26_26") (pintype "passive"))
    )
    (net (code "58") (name "/PD4") (class "Default")
      (node (ref "STM32") (pin "85") (pinfunction "PD4_85") (pintype "bidirectional"))
      (node (ref "SV2") (pin "27") (pinfunction "27_27") (pintype "passive"))
    )
    (net (code "59") (name "/PD5") (class "Default")
      (node (ref "STM32") (pin "86") (pinfunction "PD5_86") (pintype "bidirectional"))
      (node (ref "SV2") (pin "28") (pinfunction "28_28") (pintype "passive"))
    )
    (net (code "60") (name "/PD6") (class "Default")
      (node (ref "STM32") (pin "87") (pinfunction "PD6_87") (pintype "bidirectional"))
      (node (ref "SV2") (pin "29") (pinfunction "29_29") (pintype "passive"))
    )
    (net (code "61") (name "/PD7") (class "Default")
      (node (ref "STM32") (pin "88") (pinfunction "PD7_88") (pintype "bidirectional"))
      (node (ref "SV2") (pin "30") (pinfunction "30_30") (pintype "passive"))
    )
    (net (code "62") (name "/PD8") (class "Default")
      (node (ref "STM32") (pin "55") (pinfunction "PD8_55") (pintype "bidirectional"))
      (node (ref "SV2") (pin "15") (pinfunction "15_15") (pintype "passive"))
    )
    (net (code "63") (name "/PD9") (class "Default")
      (node (ref "STM32") (pin "56") (pinfunction "PD9_56") (pintype "bidirectional"))
      (node (ref "SV2") (pin "16") (pinfunction "16_16") (pintype "passive"))
    )
    (net (code "64") (name "/PD10") (class "Default")
      (node (ref "STM32") (pin "57") (pinfunction "PD10_57") (pintype "bidirectional"))
      (node (ref "SV2") (pin "17") (pinfunction "17_17") (pintype "passive"))
    )
    (net (code "65") (name "/PD11") (class "Default")
      (node (ref "STM32") (pin "58") (pinfunction "PD11_58") (pintype "bidirectional"))
      (node (ref "SV2") (pin "18") (pinfunction "18_18") (pintype "passive"))
    )
    (net (code "66") (name "/PD12") (class "Default")
      (node (ref "STM32") (pin "59") (pinfunction "PD12_59") (pintype "bidirectional"))
      (node (ref "SV2") (pin "19") (pinfunction "19_19") (pintype "passive"))
    )
    (net (code "67") (name "/PD13") (class "Default")
      (node (ref "STM32") (pin "60") (pinfunction "PD13_60") (pintype "bidirectional"))
      (node (ref "SV2") (pin "20") (pinfunction "20_20") (pintype "passive"))
    )
    (net (code "68") (name "/PD14") (class "Default")
      (node (ref "STM32") (pin "61") (pinfunction "PD14_61") (pintype "bidirectional"))
      (node (ref "SV2") (pin "21") (pinfunction "21_21") (pintype "passive"))
    )
    (net (code "69") (name "/PD15") (class "Default")
      (node (ref "STM32") (pin "62") (pinfunction "PD15_62") (pintype "bidirectional"))
      (node (ref "SV2") (pin "22") (pinfunction "22_22") (pintype "passive"))
    )
    (net (code "70") (name "/PE0") (class "Default")
      (node (ref "STM32") (pin "97") (pinfunction "PE0_97") (pintype "bidirectional"))
      (node (ref "SV2") (pin "34") (pinfunction "34_34") (pintype "passive"))
    )
    (net (code "71") (name "/PE1") (class "Default")
      (node (ref "STM32") (pin "98") (pinfunction "PE1_98") (pintype "bidirectional"))
      (node (ref "SV2") (pin "33") (pinfunction "33_33") (pintype "passive"))
    )
    (net (code "72") (name "/PE2") (class "Default")
      (node (ref "R13") (pin "2") (pinfunction "2_2") (pintype "passive"))
      (node (ref "STM32") (pin "1") (pinfunction "PE2_1") (pintype "bidirectional"))
    )
    (net (code "73") (name "/PE3") (class "Default")
      (node (ref "STM32") (pin "2") (pinfunction "PE3_2") (pintype "bidirectional"))
      (node (ref "SV2") (pin "36") (pinfunction "36_36") (pintype "passive"))
    )
    (net (code "74") (name "/PE4") (class "Default")
      (node (ref "STM32") (pin "3") (pinfunction "PE4_3") (pintype "bidirectional"))
      (node (ref "SV2") (pin "35") (pinfunction "35_35") (pintype "passive"))
    )
    (net (code "75") (name "/PE5") (class "Default")
      (node (ref "STM32") (pin "4") (pinfunction "PE5_4") (pintype "bidirectional"))
      (node (ref "SV2") (pin "38") (pinfunction "38_38") (pintype "passive"))
    )
    (net (code "76") (name "/PE6") (class "Default")
      (node (ref "STM32") (pin "5") (pinfunction "PE6_5") (pintype "bidirectional"))
      (node (ref "SV2") (pin "37") (pinfunction "37_37") (pintype "passive"))
    )
    (net (code "77") (name "/PE7") (class "Default")
      (node (ref "STM32") (pin "38") (pinfunction "PE7_38") (pintype "bidirectional"))
      (node (ref "SV1") (pin "18") (pinfunction "18_18") (pintype "passive"))
    )
    (net (code "78") (name "/PE8") (class "Default")
      (node (ref "STM32") (pin "39") (pinfunction "PE8_39") (pintype "bidirectional"))
      (node (ref "SV1") (pin "17") (pinfunction "17_17") (pintype "passive"))
    )
    (net (code "79") (name "/PE9") (class "Default")
      (node (ref "STM32") (pin "40") (pinfunction "PE9_40") (pintype "bidirectional"))
      (node (ref "SV1") (pin "16") (pinfunction "16_16") (pintype "passive"))
    )
    (net (code "80") (name "/PE10") (class "Default")
      (node (ref "STM32") (pin "41") (pinfunction "PE10_41") (pintype "bidirectional"))
      (node (ref "SV1") (pin "15") (pinfunction "15_15") (pintype "passive"))
    )
    (net (code "81") (name "/PE11") (class "Default")
      (node (ref "STM32") (pin "42") (pinfunction "PE11_42") (pintype "bidirectional"))
      (node (ref "SV1") (pin "14") (pinfunction "14_14") (pintype "passive"))
    )
    (net (code "82") (name "/PE12") (class "Default")
      (node (ref "STM32") (pin "43") (pinfunction "PE12_43") (pintype "bidirectional"))
      (node (ref "SV1") (pin "13") (pinfunction "13_13") (pintype "passive"))
    )
    (net (code "83") (name "/PE13") (class "Default")
      (node (ref "STM32") (pin "44") (pinfunction "PE13_44") (pintype "bidirectional"))
      (node (ref "SV1") (pin "12") (pinfunction "12_12") (pintype "passive"))
    )
    (net (code "84") (name "/PE14") (class "Default")
      (node (ref "STM32") (pin "45") (pinfunction "PE14_45") (pintype "bidirectional"))
      (node (ref "SV1") (pin "11") (pinfunction "11_11") (pintype "passive"))
    )
    (net (code "85") (name "/PE15") (class "Default")
      (node (ref "STM32") (pin "46") (pinfunction "PE15_46") (pintype "bidirectional"))
      (node (ref "SV1") (pin "10") (pinfunction "10_10") (pintype "passive"))
    )
    (net (code "86") (name "/RESET") (class "Default")
      (node (ref "C1") (pin "2") (pinfunction "P$2_2") (pintype "passive"))
      (node (ref "JTAG") (pin "15") (pinfunction "15_15") (pintype "passive"))
      (node (ref "R31") (pin "2") (pinfunction "2_2") (pintype "passive"))
      (node (ref "RESET") (pin "1") (pinfunction "1_1") (pintype "passive"))
      (node (ref "STM32") (pin "14") (pinfunction "NRST_14") (pintype "bidirectional"))
    )
    (net (code "87") (name "/RXD0") (class "Default")
      (node (ref "JP2") (pin "9") (pinfunction "9_9") (pintype "passive"))
      (node (ref "R15") (pin "1") (pinfunction "1_1") (pintype "passive"))
      (node (ref "U2") (pin "8") (pinfunction "RXD0_8") (pintype "bidirectional"))
    )
    (net (code "88") (name "/RXD1") (class "Default")
      (node (ref "JP2") (pin "12") (pinfunction "12_12") (pintype "passive"))
      (node (ref "R14") (pin "1") (pinfunction "1_1") (pintype "passive"))
      (node (ref "U2") (pin "7") (pinfunction "RXD1_7") (pintype "bidirectional"))
    )
    (net (code "89") (name "/RXER") (class "Default")
      (node (ref "JP2") (pin "10") (pinfunction "10_10") (pintype "passive"))
      (node (ref "U2") (pin "10") (pinfunction "RXER_10") (pintype "bidirectional"))
    )
    (net (code "90") (name "/TXD0") (class "Default")
      (node (ref "JP2") (pin "1") (pinfunction "1_1") (pintype "passive"))
      (node (ref "R19") (pin "1") (pinfunction "1_1") (pintype "passive"))
      (node (ref "U2") (pin "17") (pinfunction "TXD0_17") (pintype "bidirectional"))
    )
    (net (code "91") (name "/TXD1") (class "Default")
      (node (ref "JP2") (pin "2") (pinfunction "2_2") (pintype "passive"))
      (node (ref "R17") (pin "1") (pinfunction "1_1") (pintype "passive"))
      (node (ref "U2") (pin "18") (pinfunction "TXD1_18") (pintype "bidirectional"))
    )
    (net (code "92") (name "/TXEN") (class "Default")
      (node (ref "JP2") (pin "4") (pinfunction "4_4") (pintype "passive"))
      (node (ref "R16") (pin "1") (pinfunction "1_1") (pintype "passive"))
      (node (ref "U2") (pin "16") (pinfunction "TXEN_16") (pintype "bidirectional"))
    )
    (net (code "93") (name "/VBAT") (class "Default")
      (node (ref "R38") (pin "2") (pinfunction "2_2") (pintype "passive"))
      (node (ref "STM32") (pin "6") (pinfunction "VBAT_6") (pintype "bidirectional"))
    )
    (net (code "94") (name "/VDDA") (class "Default")
      (node (ref "C13") (pin "1") (pinfunction "P$1_1") (pintype "passive"))
      (node (ref "C22") (pin "1") (pinfunction "P$1_1") (pintype "passive"))
      (node (ref "L3") (pin "2") (pinfunction "2_2") (pintype "passive"))
      (node (ref "R29") (pin "1") (pinfunction "1_1") (pintype "passive"))
      (node (ref "STM32") (pin "22") (pinfunction "VDDA_22") (pintype "bidirectional"))
    )
    (net (code "95") (name "/VIN") (class "Default")
      (node (ref "D1") (pin "C") (pinfunction "-_C") (pintype "passive"))
      (node (ref "JP1") (pin "3") (pinfunction "3_3") (pintype "bidirectional"))
      (node (ref "R40") (pin "1") (pinfunction "1_1") (pintype "passive"))
      (node (ref "SV2") (pin "1") (pinfunction "1_1") (pintype "passive"))
      (node (ref "SV2") (pin "2") (pinfunction "2_2") (pintype "passive"))
    )
    (net (code "96") (name "/VREF+") (class "Default")
      (node (ref "C28") (pin "1") (pinfunction "P$1_1") (pintype "passive"))
      (node (ref "R29") (pin "2") (pinfunction "2_2") (pintype "passive"))
      (node (ref "STM32") (pin "21") (pinfunction "VREF+_21") (pintype "bidirectional"))
    )
    (net (code "97") (name "/VREF-") (class "Default")
      (node (ref "C28") (pin "2") (pinfunction "P$2_2") (pintype "passive"))
      (node (ref "R28") (pin "2") (pinfunction "2_2") (pintype "passive"))
      (node (ref "STM32") (pin "20") (pinfunction "VSSA_20") (pintype "bidirectional"))
    )
    (net (code "98") (name "3.3V") (class "Default")
      (node (ref "BOOT/USART3") (pin "4") (pinfunction "4_4") (pintype "passive"))
      (node (ref "C10") (pin "1") (pinfunction "P$1_1") (pintype "passive"))
      (node (ref "C16") (pin "2") (pinfunction "P$2_2") (pintype "passive"))
      (node (ref "C23") (pin "+") (pinfunction "+_+") (pintype "passive"))
      (node (ref "C24") (pin "+") (pinfunction "+_+") (pintype "passive"))
      (node (ref "C30") (pin "1") (pinfunction "P$1_1") (pintype "passive"))
      (node (ref "C34") (pin "1") (pinfunction "P$1_1") (pintype "passive"))
      (node (ref "C35") (pin "1") (pinfunction "P$1_1") (pintype "passive"))
      (node (ref "C38") (pin "1") (pinfunction "P$1_1") (pintype "passive"))
      (node (ref "C39") (pin "1") (pinfunction "P$1_1") (pintype "passive"))
      (node (ref "C40") (pin "1") (pinfunction "P$1_1") (pintype "passive"))
      (node (ref "C41") (pin "+") (pinfunction "+_+") (pintype "passive"))
      (node (ref "C42") (pin "1") (pinfunction "P$1_1") (pintype "passive"))
      (node (ref "JP1") (pin "2") (pinfunction "2_2") (pintype "bidirectional"))
      (node (ref "JP2") (pin "11") (pinfunction "11_11") (pintype "passive"))
      (node (ref "JTAG") (pin "1") (pinfunction "1_1") (pintype "passive"))
      (node (ref "JTAG") (pin "2") (pinfunction "2_2") (pintype "passive"))
      (node (ref "L1") (pin "2") (pinfunction "2_2") (pintype "passive"))
      (node (ref "L3") (pin "1") (pinfunction "1_1") (pintype "passive"))
      (node (ref "R10") (pin "2") (pinfunction "2_2") (pintype "passive"))
      (node (ref "R11") (pin "2") (pinfunction "2_2") (pintype "passive"))
      (node (ref "R18") (pin "2") (pinfunction "2_2") (pintype "passive"))
      (node (ref "R23") (pin "1") (pinfunction "1_1") (pintype "passive"))
      (node (ref "R31") (pin "1") (pinfunction "1_1") (pintype "passive"))
      (node (ref "R36") (pin "2") (pinfunction "2_2") (pintype "passive"))
      (node (ref "R37") (pin "2") (pinfunction "2_2") (pintype "passive"))
      (node (ref "R38") (pin "1") (pinfunction "1_1") (pintype "passive"))
      (node (ref "R39") (pin "1") (pinfunction "1_1") (pintype "passive"))
      (node (ref "R45") (pin "1") (pinfunction "1_1") (pintype "passive"))
      (node (ref "R48") (pin "2") (pinfunction "2_2") (pintype "passive"))
      (node (ref "R49") (pin "2") (pinfunction "2_2") (pintype "passive"))
      (node (ref "R52") (pin "1") (pinfunction "1_1") (pintype "passive"))
      (node (ref "R7") (pin "2") (pinfunction "2_2") (pintype "passive"))
      (node (ref "R9") (pin "1") (pinfunction "1_1") (pintype "passive"))
      (node (ref "S1") (pin "2") (pinfunction "S_2") (pintype "passive"))
      (node (ref "STM32") (pin "100") (pinfunction "VDD6_100") (pintype "bidirectional"))
      (node (ref "STM32") (pin "11") (pinfunction "VDD_11") (pintype "bidirectional"))
      (node (ref "STM32") (pin "19") (pinfunction "VDD2_19") (pintype "bidirectional"))
      (node (ref "STM32") (pin "28") (pinfunction "VDD3_28") (pintype "bidirectional"))
      (node (ref "STM32") (pin "50") (pinfunction "VDD4_50") (pintype "bidirectional"))
      (node (ref "STM32") (pin "75") (pinfunction "VDD5_75") (pintype "bidirectional"))
      (node (ref "SV1") (pin "19") (pinfunction "19_19") (pintype "passive"))
      (node (ref "SV1") (pin "20") (pinfunction "20_20") (pintype "passive"))
      (node (ref "SV1") (pin "35") (pinfunction "35_35") (pintype "passive"))
      (node (ref "SV1") (pin "36") (pinfunction "36_36") (pintype "passive"))
      (node (ref "SV2") (pin "3") (pinfunction "3_3") (pintype "passive"))
      (node (ref "SV2") (pin "4") (pinfunction "4_4") (pintype "passive"))
      (node (ref "U2") (pin "9") (pinfunction "VDDIO_9") (pintype "bidirectional"))
    )
    (net (code "99") (name "GND") (class "Default")
      (node (ref "3.3V_LED") (pin "C") (pinfunction "C_C") (pintype "passive"))
      (node (ref "BOOT/USART3") (pin "3") (pinfunction "3_3") (pintype "passive"))
      (node (ref "C1") (pin "1") (pinfunction "P$1_1") (pintype "passive"))
      (node (ref "C10") (pin "2") (pinfunction "P$2_2") (pintype "passive"))
      (node (ref "C11") (pin "1") (pinfunction "P$1_1") (pintype "passive"))
      (node (ref "C12") (pin "1") (pinfunction "P$1_1") (pintype "passive"))
      (node (ref "C13") (pin "2") (pinfunction "P$2_2") (pintype "passive"))
      (node (ref "C14") (pin "+") (pinfunction "+_+") (pintype "passive"))
      (node (ref "C15") (pin "2") (pinfunction "P$2_2") (pintype "passive"))
      (node (ref "C16") (pin "1") (pinfunction "P$1_1") (pintype "passive"))
      (node (ref "C17") (pin "2") (pinfunction "P$2_2") (pintype "passive"))
      (node (ref "C19") (pin "2") (pinfunction "P$2_2") (pintype "passive"))
      (node (ref "C2") (pin "2") (pinfunction "P$2_2") (pintype "passive"))
      (node (ref "C20") (pin "2") (pinfunction "P$2_2") (pintype "passive"))
      (node (ref "C21") (pin "2") (pinfunction "P$2_2") (pintype "passive"))
      (node (ref "C22") (pin "2") (pinfunction "P$2_2") (pintype "passive"))
      (node (ref "C23") (pin "-") (pinfunction "-_-") (pintype "passive"))
      (node (ref "C24") (pin "-") (pinfunction "-_-") (pintype "passive"))
      (node (ref "C25") (pin "2") (pinfunction "P$2_2") (pintype "passive"))
      (node (ref "C26") (pin "2") (pinfunction "P$2_2") (pintype "passive"))
      (node (ref "C27") (pin "2") (pinfunction "P$2_2") (pintype "passive"))
      (node (ref "C29") (pin "2") (pinfunction "P$2_2") (pintype "passive"))
      (node (ref "C3") (pin "2") (pinfunction "P$2_2") (pintype "passive"))
      (node (ref "C30") (pin "2") (pinfunction "P$2_2") (pintype "passive"))
      (node (ref "C34") (pin "2") (pinfunction "P$2_2") (pintype "passive"))
      (node (ref "C35") (pin "2") (pinfunction "P$2_2") (pintype "passive"))
      (node (ref "C38") (pin "2") (pinfunction "P$2_2") (pintype "passive"))
      (node (ref "C39") (pin "2") (pinfunction "P$2_2") (pintype "passive"))
      (node (ref "C4") (pin "-") (pinfunction "-_-") (pintype "passive"))
      (node (ref "C40") (pin "2") (pinfunction "P$2_2") (pintype "passive"))
      (node (ref "C41") (pin "-") (pinfunction "-_-") (pintype "passive"))
      (node (ref "C42") (pin "2") (pinfunction "P$2_2") (pintype "passive"))
      (node (ref "C5") (pin "2") (pinfunction "P$2_2") (pintype "passive"))
      (node (ref "C6") (pin "-") (pinfunction "-_-") (pintype "passive"))
      (node (ref "C7") (pin "1") (pinfunction "P$1_1") (pintype "passive"))
      (node (ref "C8") (pin "1") (pinfunction "P$1_1") (pintype "passive"))
      (node (ref "C9") (pin "2") (pinfunction "P$2_2") (pintype "passive"))
      (node (ref "CN1") (pin "GND") (pinfunction "GND_GND") (pintype "power_in"))
      (node (ref "JP1") (pin "1") (pinfunction "1_1") (pintype "bidirectional"))
      (node (ref "JP2") (pin "13") (pinfunction "13_13") (pintype "passive"))
      (node (ref "JP2") (pin "14") (pinfunction "14_14") (pintype "passive"))
      (node (ref "JTAG") (pin "10") (pinfunction "10_10") (pintype "passive"))
      (node (ref "JTAG") (pin "12") (pinfunction "12_12") (pintype "passive"))
      (node (ref "JTAG") (pin "14") (pinfunction "14_14") (pintype "passive"))
      (node (ref "JTAG") (pin "16") (pinfunction "16_16") (pintype "passive"))
      (node (ref "JTAG") (pin "18") (pinfunction "18_18") (pintype "passive"))
      (node (ref "JTAG") (pin "20") (pinfunction "20_20") (pintype "passive"))
      (node (ref "JTAG") (pin "4") (pinfunction "4_4") (pintype "passive"))
      (node (ref "JTAG") (pin "6") (pinfunction "6_6") (pintype "passive"))
      (node (ref "JTAG") (pin "8") (pinfunction "8_8") (pintype "passive"))
      (node (ref "LED1") (pin "K") (pinfunction "C_K") (pintype "passive"))
      (node (ref "LED2") (pin "K") (pinfunction "C_K") (pintype "passive"))
      (node (ref "LED3") (pin "C") (pinfunction "C_C") (pintype "passive"))
      (node (ref "Q4") (pin "2") (pinfunction "S_2") (pintype "bidirectional"))
      (node (ref "Q5") (pin "2") (pinfunction "S_2") (pintype "bidirectional"))
      (node (ref "R28") (pin "1") (pinfunction "1_1") (pintype "passive"))
      (node (ref "R42") (pin "2") (pinfunction "2_2") (pintype "passive"))
      (node (ref "R44") (pin "2") (pinfunction "2_2") (pintype "passive"))
      (node (ref "R5") (pin "2") (pinfunction "2_2") (pintype "passive"))
      (node (ref "R51") (pin "1") (pinfunction "1_1") (pintype "passive"))
      (node (ref "R6") (pin "2") (pinfunction "2_2") (pintype "passive"))
      (node (ref "RESET") (pin "2") (pinfunction "2_2") (pintype "passive"))
      (node (ref "STAT_LED1") (pin "C") (pinfunction "C_C") (pintype "passive"))
      (node (ref "STAT_LED2") (pin "C") (pinfunction "C_C") (pintype "passive"))
      (node (ref "STM32") (pin "10") (pinfunction "VSS_10") (pintype "bidirectional"))
      (node (ref "STM32") (pin "27") (pinfunction "VSS2_27") (pintype "bidirectional"))
      (node (ref "STM32") (pin "74") (pinfunction "VSS3_74") (pintype "bidirectional"))
      (node (ref "STM32") (pin "99") (pinfunction "VSS4_99") (pintype "bidirectional"))
      (node (ref "SV1") (pin "1") (pinfunction "1_1") (pintype "passive"))
      (node (ref "SV1") (pin "2") (pinfunction "2_2") (pintype "passive"))
      (node (ref "SV1") (pin "21") (pinfunction "21_21") (pintype "passive"))
      (node (ref "SV1") (pin "22") (pinfunction "22_22") (pintype "passive"))
      (node (ref "SV1") (pin "3") (pinfunction "3_3") (pintype "passive"))
      (node (ref "SV1") (pin "33") (pinfunction "33_33") (pintype "passive"))
      (node (ref "SV1") (pin "34") (pinfunction "34_34") (pintype "passive"))
      (node (ref "SV1") (pin "7") (pinfunction "7_7") (pintype "passive"))
      (node (ref "SV1") (pin "8") (pinfunction "8_8") (pintype "passive"))
      (node (ref "SV1") (pin "9") (pinfunction "9_9") (pintype "passive"))
      (node (ref "SV2") (pin "10") (pinfunction "10_10") (pintype "passive"))
      (node (ref "SV2") (pin "13") (pinfunction "13_13") (pintype "passive"))
      (node (ref "SV2") (pin "14") (pinfunction "14_14") (pintype "passive"))
      (node (ref "SV2") (pin "31") (pinfunction "31_31") (pintype "passive"))
      (node (ref "SV2") (pin "32") (pinfunction "32_32") (pintype "passive"))
      (node (ref "SV2") (pin "5") (pinfunction "5_5") (pintype "passive"))
      (node (ref "SV2") (pin "6") (pinfunction "6_6") (pintype "passive"))
      (node (ref "U1") (pin "1") (pinfunction "P$1_1") (pintype "bidirectional"))
      (node (ref "U2") (pin "THERM") (pinfunction "GND_THERM") (pintype "bidirectional"))
      (node (ref "VIN_LED") (pin "C") (pinfunction "C_C") (pintype "passive"))
      (node (ref "X1") (pin "1") (pinfunction "1_1") (pintype "power_in"))
      (node (ref "X1") (pin "3") (pinfunction "3_3") (pintype "power_in"))
    )
    (net (code "100") (name "GND1") (class "Default")
      (node (ref "C14") (pin "-") (pinfunction "-_-") (pintype "passive"))
      (node (ref "RJ1") (pin "GND") (pinfunction "GND_GND") (pintype "bidirectional"))
      (node (ref "RJ1") (pin "SHIELD0") (pinfunction "SHIELD0_SHIELD0") (pintype "bidirectional"))
      (node (ref "RJ1") (pin "SHIELD1") (pinfunction "SHIELD1_SHIELD1") (pintype "bidirectional"))
    )
    (net (code "101") (name "LED1") (class "Default")
      (node (ref "Q5") (pin "1") (pinfunction "G_1") (pintype "bidirectional"))
      (node (ref "U2") (pin "3") (pinfunction "LED1/REGOFF_3") (pintype "bidirectional"))
    )
    (net (code "102") (name "LED2") (class "Default")
      (node (ref "Q4") (pin "1") (pinfunction "G_1") (pintype "bidirectional"))
      (node (ref "R6") (pin "1") (pinfunction "1_1") (pintype "passive"))
      (node (ref "U2") (pin "2") (pinfunction "LED2/NINTSEL_2") (pintype "bidirectional"))
    )
    (net (code "103") (name "Net-(3.3V_LED-PadA)") (class "Default")
      (node (ref "3.3V_LED") (pin "A") (pinfunction "A_A") (pintype "passive"))
      (node (ref "R7") (pin "1") (pinfunction "1_1") (pintype "passive"))
    )
    (net (code "104") (name "Net-(C2-P$1)") (class "Default")
      (node (ref "C2") (pin "1") (pinfunction "P$1_1") (pintype "passive"))
      (node (ref "C3") (pin "1") (pinfunction "P$1_1") (pintype "passive"))
      (node (ref "C4") (pin "+") (pinfunction "+_+") (pintype "passive"))
      (node (ref "R18") (pin "1") (pinfunction "1_1") (pintype "passive"))
      (node (ref "U1") (pin "2") (pinfunction "P$2_2") (pintype "bidirectional"))
      (node (ref "U1") (pin "4") (pinfunction "P$4_4") (pintype "bidirectional"))
    )
    (net (code "105") (name "Net-(C7-P$2)") (class "Default")
      (node (ref "C7") (pin "2") (pinfunction "P$2_2") (pintype "passive"))
      (node (ref "Q2") (pin "1") (pinfunction "1_1") (pintype "passive"))
      (node (ref "R34") (pin "1") (pinfunction "1_1") (pintype "passive"))
      (node (ref "R35") (pin "2") (pinfunction "2_2") (pintype "passive"))
    )
    (net (code "106") (name "Net-(C19-P$1)") (class "Default")
      (node (ref "C19") (pin "1") (pinfunction "P$1_1") (pintype "passive"))
      (node (ref "STM32") (pin "73") (pinfunction "VCAP_2_73") (pintype "bidirectional"))
    )
    (net (code "107") (name "Net-(C20-P$1)") (class "Default")
      (node (ref "C20") (pin "1") (pinfunction "P$1_1") (pintype "passive"))
      (node (ref "STM32") (pin "49") (pinfunction "VCAP_1_49") (pintype "bidirectional"))
    )
    (net (code "108") (name "Net-(CN1-PadD+)") (class "Default")
      (node (ref "CN1") (pin "D+") (pinfunction "D+_D+") (pintype "bidirectional"))
      (node (ref "R3") (pin "1") (pinfunction "1_1") (pintype "passive"))
    )
    (net (code "109") (name "Net-(CN1-PadD-)") (class "Default")
      (node (ref "CN1") (pin "D-") (pinfunction "D-_D-") (pintype "bidirectional"))
      (node (ref "R2") (pin "1") (pinfunction "1_1") (pintype "passive"))
    )
    (net (code "110") (name "Net-(CN1-PadID)") (class "Default")
      (node (ref "CN1") (pin "ID") (pinfunction "ID_ID") (pintype "bidirectional"))
      (node (ref "R24") (pin "1") (pinfunction "1_1") (pintype "passive"))
    )
    (net (code "111") (name "Net-(CN1-PadVBUS)") (class "Default")
      (node (ref "CN1") (pin "VBUS") (pinfunction "VBUS_VBUS") (pintype "power_in"))
      (node (ref "R41") (pin "1") (pinfunction "1_1") (pintype "passive"))
    )
    (net (code "112") (name "Net-(D1-+)") (class "Default")
      (node (ref "D1") (pin "A") (pinfunction "+_A") (pintype "passive"))
      (node (ref "X1") (pin "2") (pinfunction "2_2") (pintype "power_in"))
    )
    (net (code "113") (name "Net-(LED1-PadA)") (class "Default")
      (node (ref "LED1") (pin "A") (pinfunction "A_A") (pintype "passive"))
      (node (ref "R32") (pin "2") (pinfunction "2_2") (pintype "passive"))
      (node (ref "STAT_LED1") (pin "A") (pinfunction "A_A") (pintype "passive"))
    )
    (net (code "114") (name "Net-(LED2-PadA)") (class "Default")
      (node (ref "LED2") (pin "A") (pinfunction "A_A") (pintype "passive"))
      (node (ref "R33") (pin "2") (pinfunction "2_2") (pintype "passive"))
      (node (ref "STAT_LED2") (pin "A") (pinfunction "A_A") (pintype "passive"))
    )
    (net (code "115") (name "Net-(LED3-PadA)") (class "Default")
      (node (ref "LED3") (pin "A") (pinfunction "A_A") (pintype "passive"))
      (node (ref "R30") (pin "2") (pinfunction "2_2") (pintype "passive"))
    )
    (net (code "116") (name "Net-(Q4-D)") (class "Default")
      (node (ref "Q4") (pin "3") (pinfunction "D_3") (pintype "bidirectional"))
      (node (ref "RJ1") (pin "G-") (pinfunction "G-_G-") (pintype "bidirectional"))
    )
    (net (code "117") (name "Net-(Q5-D)") (class "Default")
      (node (ref "Q5") (pin "3") (pinfunction "D_3") (pintype "bidirectional"))
      (node (ref "RJ1") (pin "Y-") (pinfunction "Y-_Y-") (pintype "bidirectional"))
    )
    (net (code "118") (name "Net-(R1-Pad1)") (class "Default")
      (node (ref "R1") (pin "1") (pinfunction "1_1") (pintype "passive"))
      (node (ref "VIN_LED") (pin "A") (pinfunction "A_A") (pintype "passive"))
    )
    (net (code "119") (name "Net-(R10-Pad1)") (class "Default")
      (node (ref "R10") (pin "1") (pinfunction "1_1") (pintype "passive"))
      (node (ref "RJ1") (pin "G+") (pinfunction "G+_G+") (pintype "bidirectional"))
    )
    (net (code "120") (name "Net-(R11-Pad1)") (class "Default")
      (node (ref "R11") (pin "1") (pinfunction "1_1") (pintype "passive"))
      (node (ref "RJ1") (pin "Y+") (pinfunction "Y+_Y+") (pintype "bidirectional"))
    )
    (net (code "121") (name "Net-(S1-P)") (class "Default")
      (node (ref "R43") (pin "2") (pinfunction "2_2") (pintype "passive"))
      (node (ref "R44") (pin "1") (pinfunction "1_1") (pintype "passive"))
      (node (ref "S1") (pin "1") (pinfunction "P_1") (pintype "passive"))
    )
    (net (code "122") (name "Net-(U2-RBIAS)") (class "Default")
      (node (ref "R5") (pin "1") (pinfunction "1_1") (pintype "passive"))
      (node (ref "U2") (pin "24") (pinfunction "RBIAS_24") (pintype "bidirectional"))
    )
    (net (code "123") (name "RX_N") (class "Default")
      (node (ref "R27") (pin "2") (pinfunction "2_2") (pintype "passive"))
      (node (ref "RJ1") (pin "RD-") (pinfunction "RD-_RD-") (pintype "bidirectional"))
      (node (ref "U2") (pin "22") (pinfunction "RX-_22") (pintype "bidirectional"))
    )
    (net (code "124") (name "RX_P") (class "Default")
      (node (ref "R26") (pin "2") (pinfunction "2_2") (pintype "passive"))
      (node (ref "RJ1") (pin "RD+") (pinfunction "RD+_RD+") (pintype "bidirectional"))
      (node (ref "U2") (pin "23") (pinfunction "RX+_23") (pintype "bidirectional"))
    )
    (net (code "125") (name "TX_N") (class "Default")
      (node (ref "R25") (pin "2") (pinfunction "2_2") (pintype "passive"))
      (node (ref "RJ1") (pin "TD-") (pinfunction "TD-_TD-") (pintype "bidirectional"))
      (node (ref "U2") (pin "20") (pinfunction "TX-_20") (pintype "bidirectional"))
    )
    (net (code "126") (name "TX_P") (class "Default")
      (node (ref "R8") (pin "2") (pinfunction "2_2") (pintype "passive"))
      (node (ref "RJ1") (pin "TD+") (pinfunction "TD+_TD+") (pintype "bidirectional"))
      (node (ref "U2") (pin "21") (pinfunction "TX+_21") (pintype "bidirectional"))
    )
    (net (code "127") (name "USB_DET") (class "Default")
      (node (ref "R41") (pin "2") (pinfunction "2_2") (pintype "passive"))
      (node (ref "STM32") (pin "68") (pinfunction "PA9_68") (pintype "bidirectional"))
    )
    (net (code "128") (name "USB_ID") (class "Default")
      (node (ref "R24") (pin "2") (pinfunction "2_2") (pintype "passive"))
      (node (ref "STM32") (pin "69") (pinfunction "PA10_69") (pintype "bidirectional"))
    )
    (net (code "129") (name "USB_N") (class "Default")
      (node (ref "R2") (pin "2") (pinfunction "2_2") (pintype "passive"))
      (node (ref "STM32") (pin "70") (pinfunction "PA11_70") (pintype "bidirectional"))
    )
    (net (code "130") (name "USB_P") (class "Default")
      (node (ref "R3") (pin "2") (pinfunction "2_2") (pintype "passive"))
      (node (ref "STM32") (pin "71") (pinfunction "PA12_71") (pintype "bidirectional"))
    )
    (net (code "131") (name "VDDA_PHY") (class "Default")
      (node (ref "C15") (pin "1") (pinfunction "P$1_1") (pintype "passive"))
      (node (ref "C25") (pin "1") (pinfunction "P$1_1") (pintype "passive"))
      (node (ref "C26") (pin "1") (pinfunction "P$1_1") (pintype "passive"))
      (node (ref "C27") (pin "1") (pinfunction "P$1_1") (pintype "passive"))
      (node (ref "C29") (pin "1") (pinfunction "P$1_1") (pintype "passive"))
      (node (ref "L1") (pin "1") (pinfunction "1_1") (pintype "passive"))
      (node (ref "R25") (pin "1") (pinfunction "1_1") (pintype "passive"))
      (node (ref "R26") (pin "1") (pinfunction "1_1") (pintype "passive"))
      (node (ref "R27") (pin "1") (pinfunction "1_1") (pintype "passive"))
      (node (ref "R8") (pin "1") (pinfunction "1_1") (pintype "passive"))
      (node (ref "RJ1") (pin "P4") (pinfunction "P4_P4") (pintype "bidirectional"))
      (node (ref "RJ1") (pin "P5") (pinfunction "P5_P5") (pintype "bidirectional"))
      (node (ref "U2") (pin "1") (pinfunction "VDD2A_1") (pintype "bidirectional"))
      (node (ref "U2") (pin "19") (pinfunction "VDD1A_19") (pintype "bidirectional"))
    )
    (net (code "132") (name "VDDCR") (class "Default")
      (node (ref "C17") (pin "1") (pinfunction "P$1_1") (pintype "passive"))
      (node (ref "C21") (pin "1") (pinfunction "P$1_1") (pintype "passive"))
      (node (ref "U2") (pin "6") (pinfunction "VDDCR_6") (pintype "bidirectional"))
    )
    (net (code "133") (name "XTAL1") (class "Default")
      (node (ref "C12") (pin "2") (pinfunction "P$2_2") (pintype "passive"))
      (node (ref "Q3") (pin "2") (pinfunction "2_2") (pintype "passive"))
      (node (ref "R4") (pin "2") (pinfunction "2_2") (pintype "passive"))
      (node (ref "U2") (pin "5") (pinfunction "XTAL1_5") (pintype "bidirectional"))
    )
    (net (code "134") (name "XTAL2") (class "Default")
      (node (ref "C11") (pin "2") (pinfunction "P$2_2") (pintype "passive"))
      (node (ref "Q3") (pin "1") (pinfunction "1_1") (pintype "passive"))
      (node (ref "R4") (pin "1") (pinfunction "1_1") (pintype "passive"))
      (node (ref "U2") (pin "4") (pinfunction "XTAL2_4") (pintype "bidirectional"))
    )
    (net (code "135") (name "unconnected-(H1-Pad1)") (class "Default")
      (node (ref "H1") (pin "1") (pinfunction "1_1") (pintype "passive"))
    )
    (net (code "136") (name "unconnected-(H2-Pad1)") (class "Default")
      (node (ref "H2") (pin "1") (pinfunction "1_1") (pintype "passive"))
    )
    (net (code "137") (name "unconnected-(H3-Pad1)") (class "Default")
      (node (ref "H3") (pin "1") (pinfunction "1_1") (pintype "passive"))
    )
    (net (code "138") (name "unconnected-(H4-Pad1)") (class "Default")
      (node (ref "H4") (pin "1") (pinfunction "1_1") (pintype "passive"))
    )
    (net (code "139") (name "unconnected-(H5-Pad1)") (class "Default")
      (node (ref "H5") (pin "1") (pinfunction "1_1") (pintype "passive"))
    )
    (net (code "140") (name "unconnected-(H6-Pad1)") (class "Default")
      (node (ref "H6") (pin "1") (pinfunction "1_1") (pintype "passive"))
    )
    (net (code "141") (name "unconnected-(JTAG-Pad11)") (class "Default")
      (node (ref "JTAG") (pin "11") (pinfunction "11_11") (pintype "passive"))
    )
    (net (code "142") (name "unconnected-(JTAG-Pad17)") (class "Default")
      (node (ref "JTAG") (pin "17") (pinfunction "17_17") (pintype "passive"))
    )
    (net (code "143") (name "unconnected-(JTAG-Pad19)") (class "Default")
      (node (ref "JTAG") (pin "19") (pinfunction "19_19") (pintype "passive"))
    )
    (net (code "144") (name "unconnected-(RJ1-PadNC)") (class "Default")
      (node (ref "RJ1") (pin "NC") (pinfunction "NC_NC") (pintype "bidirectional"))
    )
  )
)
